# SCH_BME_280_Sensor.net
KiCad netlist of a schematic drawn in EasyEDA
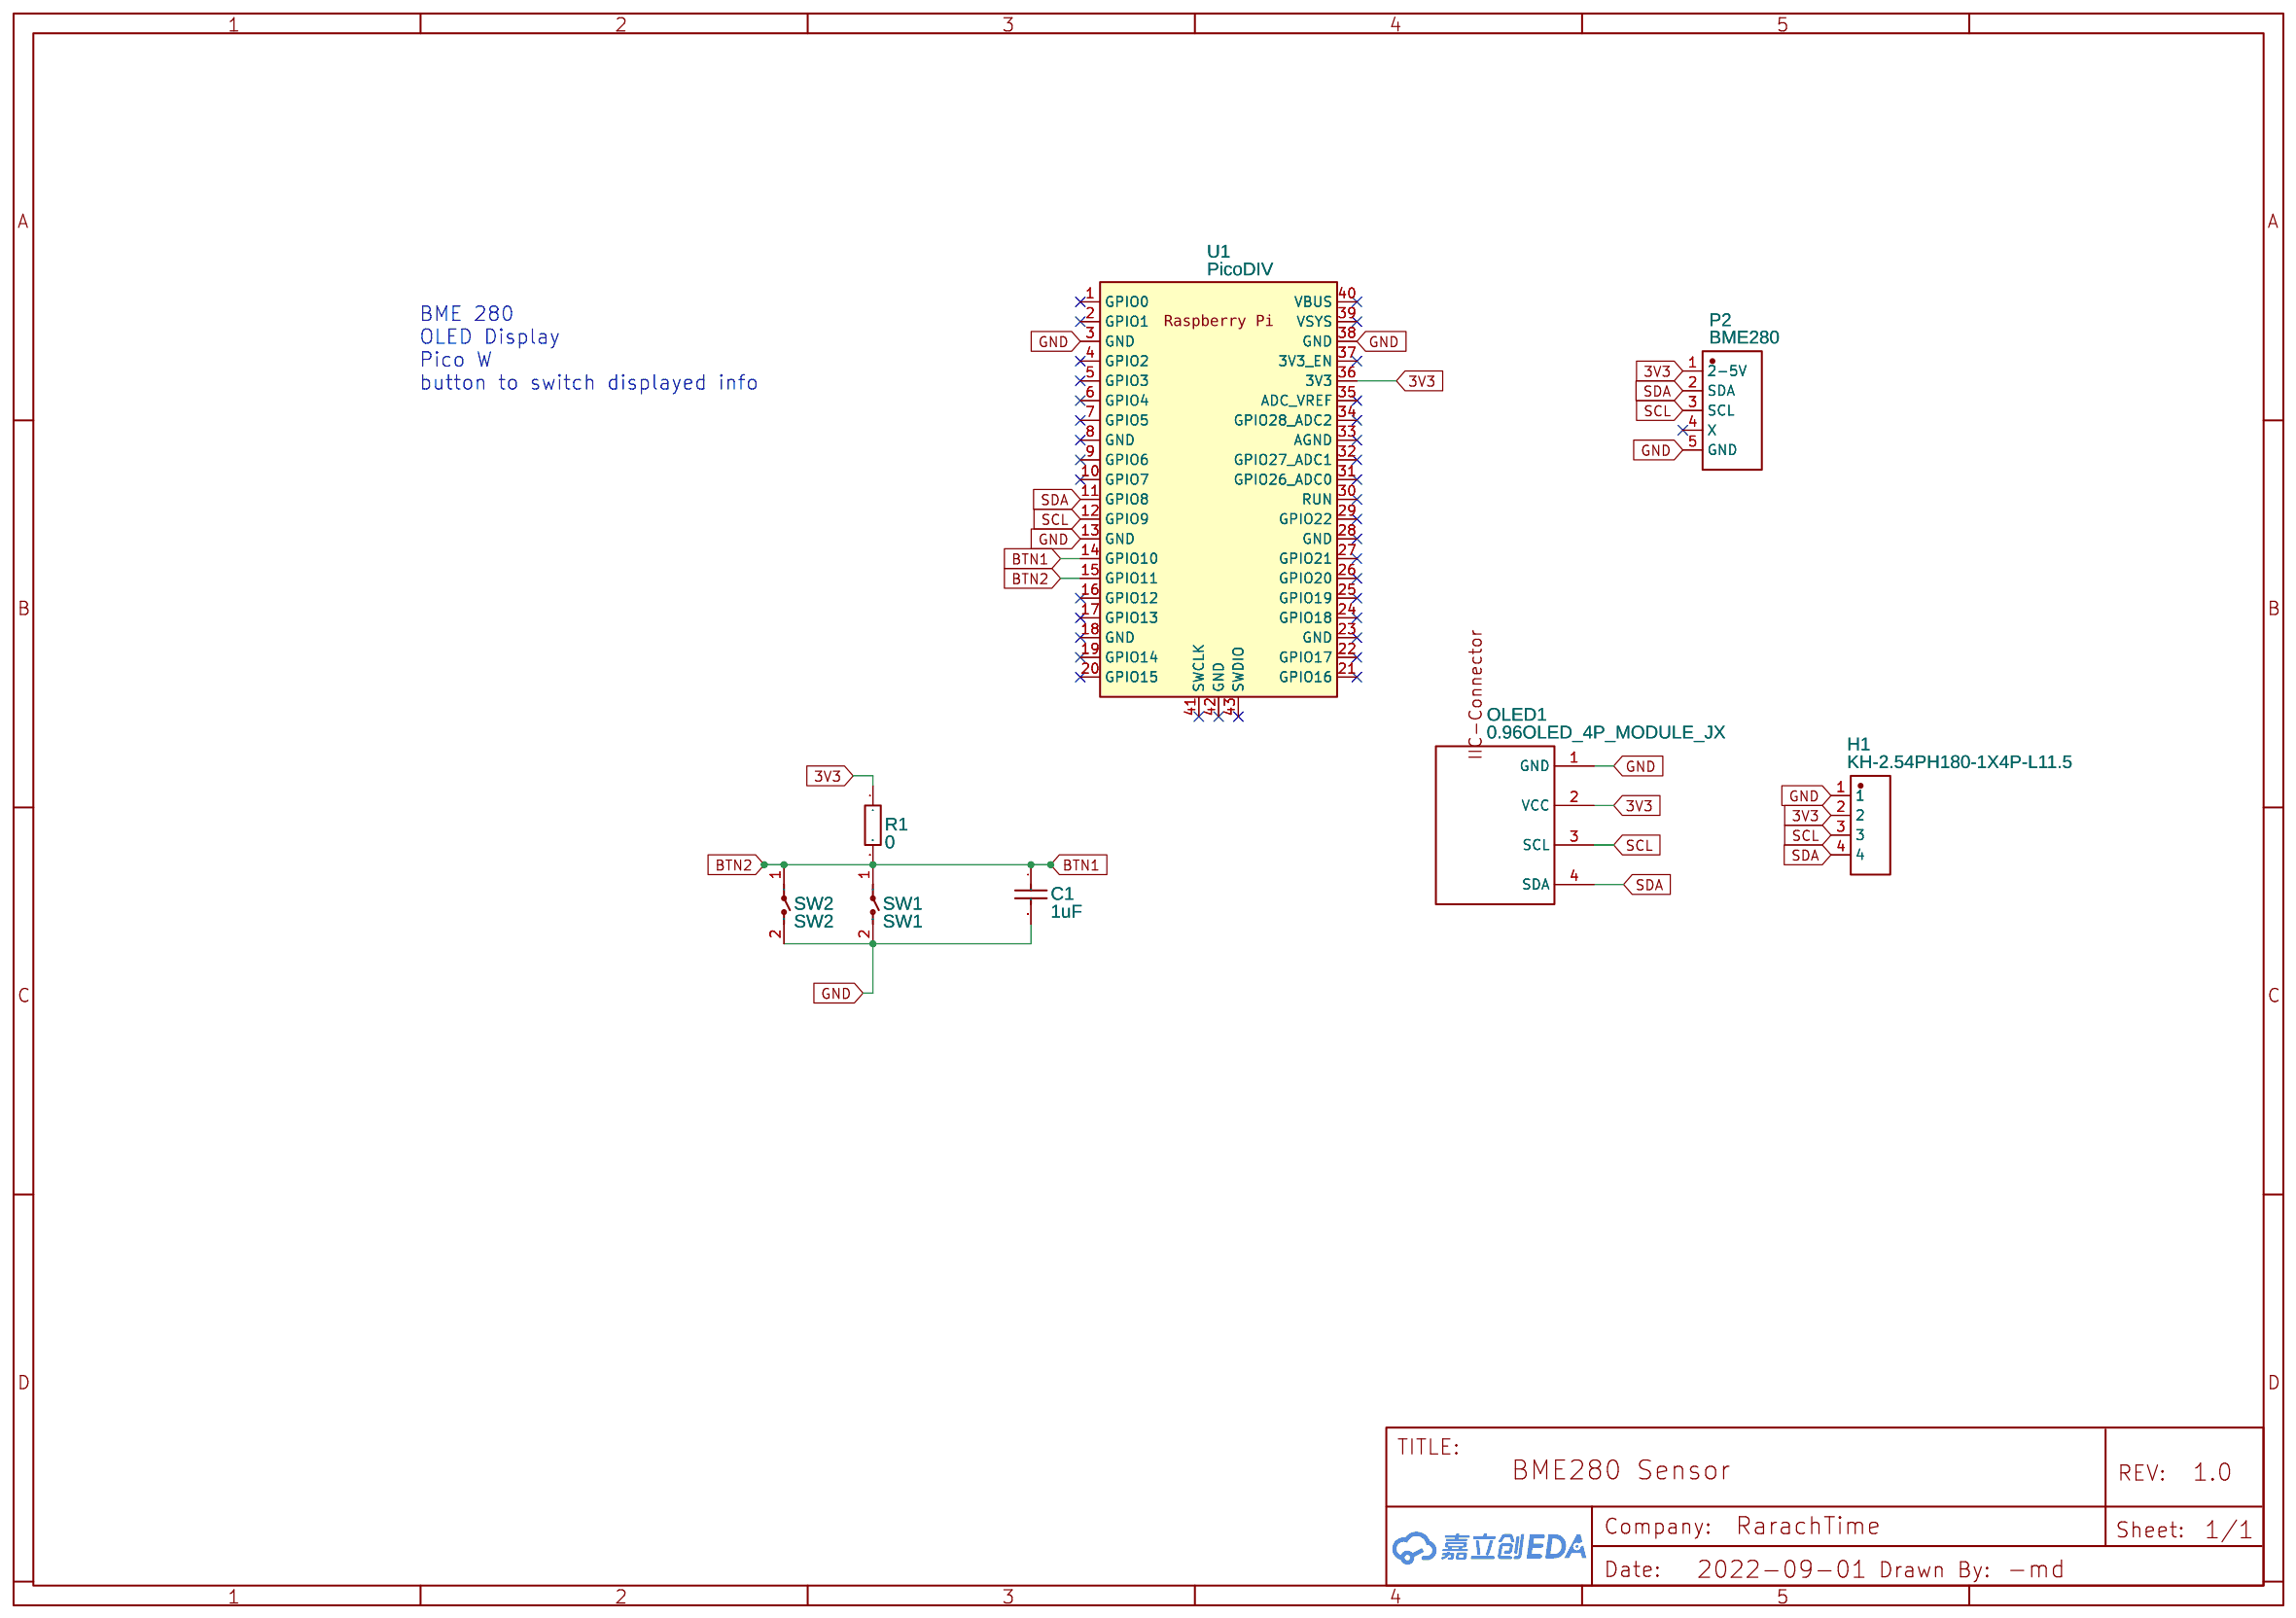
[diagram p0: schematic sheet]

(export (version "E")
  (design (tool "Eeschema 10.0.6"))
  (components
    (comp (ref "C1")
      (value "1uF")
      (fields
        (field (name "BOM_Manufacturer Part") "CL21B105KBFNNNE")
        (field (name "BOM_Supplier Part") "C28323")
      )
      (libsource (lib "") (part "CL21B105KBFNNNE"))
    )
    (comp (ref "H1")
      (value "KH-2.54PH180-1X4P-L11.5")
      (fields (field (name "BOM_Supplier Part") "C2905435"))
      (libsource (lib "") (part "KH-2.54PH180-1X4P-L11.5"))
    )
    (comp (ref "OLED1")
      (value "0.96OLED_4P_MODULE_JX")
      (fields (field (name "BOM_Supplier Part") "C9900004566"))
      (libsource (lib "") (part "0.96OLED_4P_MODULE_JX"))
    )
    (comp (ref "P2")
      (value "BME280")
      (fields
        (field (name "BOM_Manufacturer Part") "2.54mm 1*5P Header")
        (field (name "BOM_Supplier Part") "C50951")
      )
      (libsource (lib "") (part "BME680_PIMORONI"))
    )
    (comp (ref "R1")
      (value "0")
      (fields
        (field (name "BOM_Manufacturer Part") "0805W8F0000T5E")
        (field (name "BOM_Supplier Part") "C17477")
      )
      (libsource (lib "") (part "0805W8F0000T5E"))
    )
    (comp (ref "SW1")
      (value "SW1")
      (fields
        (field (name "BOM_Manufacturer Part") "TS-1001T-AC04316")
        (field (name "BOM_Supplier Part") "C720484")
      )
      (libsource (lib "") (part "TS-1001T-AC04316"))
    )
    (comp (ref "SW2")
      (value "SW2")
      (fields
        (field (name "BOM_Manufacturer Part") "TS-1001T-AC04316")
        (field (name "BOM_Supplier Part") "C720484")
      )
      (libsource (lib "") (part "TS-1001T-AC04316"))
    )
    (comp (ref "U1") (value "PicoDIV") (libsource (lib "") (part "Pico")))
  )
  (nets
    (net (code "1") (name "3V3") (class "Default")
      (node (ref "H1") (pin "2") (pinfunction "2_2") (pintype "unspecified"))
      (node (ref "OLED1") (pin "2") (pinfunction "VCC_2") (pintype "unspecified"))
      (node (ref "P2") (pin "1") (pinfunction "2-5V_1") (pintype "unspecified"))
      (node (ref "R1") (pin "1") (pinfunction "1_1") (pintype "input"))
      (node (ref "U1") (pin "36") (pinfunction "3V3_36") (pintype "unspecified"))
    )
    (net (code "2") (name "BTN1") (class "Default")
      (node (ref "C1") (pin "1") (pinfunction "1_1") (pintype "input"))
      (node (ref "R1") (pin "2") (pinfunction "2_2") (pintype "input"))
      (node (ref "SW1") (pin "1") (pinfunction "1_1") (pintype "unspecified"))
      (node (ref "SW2") (pin "1") (pinfunction "1_1") (pintype "unspecified"))
      (node (ref "U1") (pin "14") (pinfunction "GPIO10_14") (pintype "bidirectional"))
      (node (ref "U1") (pin "15") (pinfunction "GPIO11_15") (pintype "bidirectional"))
    )
    (net (code "3") (name "GND") (class "Default")
      (node (ref "C1") (pin "2") (pinfunction "2_2") (pintype "input"))
      (node (ref "H1") (pin "1") (pinfunction "1_1") (pintype "unspecified"))
      (node (ref "OLED1") (pin "1") (pinfunction "GND_1") (pintype "unspecified"))
      (node (ref "P2") (pin "5") (pinfunction "GND_5") (pintype "unspecified"))
      (node (ref "SW1") (pin "2") (pinfunction "2_2") (pintype "unspecified"))
      (node (ref "SW2") (pin "2") (pinfunction "2_2") (pintype "unspecified"))
      (node (ref "U1") (pin "13") (pinfunction "GND_13") (pintype "bidirectional"))
      (node (ref "U1") (pin "3") (pinfunction "GND_3") (pintype "bidirectional"))
      (node (ref "U1") (pin "38") (pinfunction "GND_38") (pintype "bidirectional"))
    )
    (net (code "4") (name "SCL") (class "Default")
      (node (ref "H1") (pin "3") (pinfunction "3_3") (pintype "unspecified"))
      (node (ref "OLED1") (pin "3") (pinfunction "SCL_3") (pintype "unspecified"))
      (node (ref "P2") (pin "3") (pinfunction "SCL_3") (pintype "unspecified"))
      (node (ref "U1") (pin "12") (pinfunction "GPIO9_12") (pintype "bidirectional"))
    )
    (net (code "5") (name "SDA") (class "Default")
      (node (ref "H1") (pin "4") (pinfunction "4_4") (pintype "unspecified"))
      (node (ref "OLED1") (pin "4") (pinfunction "SDA_4") (pintype "unspecified"))
      (node (ref "P2") (pin "2") (pinfunction "SDA_2") (pintype "unspecified"))
      (node (ref "U1") (pin "11") (pinfunction "GPIO8_11") (pintype "bidirectional"))
    )
    (net (code "6") (name "unconnected-(P2-X-Pad4)") (class "Default")
      (node (ref "P2") (pin "4") (pinfunction "X_4") (pintype "unspecified+no_connect"))
    )
    (net (code "7") (name "unconnected-(U1-3V3_EN-Pad37)") (class "Default")
      (node (ref "U1") (pin "37") (pinfunction "3V3_EN_37") (pintype "input+no_connect"))
    )
    (net (code "8") (name "unconnected-(U1-ADC_VREF-Pad35)") (class "Default")
      (node (ref "U1") (pin "35") (pinfunction "ADC_VREF_35") (pintype "unspecified+no_connect"))
    )
    (net (code "9") (name "unconnected-(U1-AGND-Pad33)") (class "Default")
      (node (ref "U1") (pin "33") (pinfunction "AGND_33") (pintype "bidirectional+no_connect"))
    )
    (net (code "10") (name "unconnected-(U1-GND-Pad8)") (class "Default")
      (node (ref "U1") (pin "8") (pinfunction "GND_8") (pintype "bidirectional+no_connect"))
    )
    (net (code "11") (name "unconnected-(U1-GND-Pad18)") (class "Default")
      (node (ref "U1") (pin "18") (pinfunction "GND_18") (pintype "bidirectional+no_connect"))
    )
    (net (code "12") (name "unconnected-(U1-GND-Pad23)") (class "Default")
      (node (ref "U1") (pin "23") (pinfunction "GND_23") (pintype "bidirectional+no_connect"))
    )
    (net (code "13") (name "unconnected-(U1-GND-Pad28)") (class "Default")
      (node (ref "U1") (pin "28") (pinfunction "GND_28") (pintype "bidirectional+no_connect"))
    )
    (net (code "14") (name "unconnected-(U1-GND-Pad42)") (class "Default")
      (node (ref "U1") (pin "42") (pinfunction "GND_42") (pintype "bidirectional+no_connect"))
    )
    (net (code "15") (name "unconnected-(U1-GPIO0-Pad1)") (class "Default")
      (node (ref "U1") (pin "1") (pinfunction "GPIO0_1") (pintype "bidirectional+no_connect"))
    )
    (net (code "16") (name "unconnected-(U1-GPIO1-Pad2)") (class "Default")
      (node (ref "U1") (pin "2") (pinfunction "GPIO1_2") (pintype "bidirectional+no_connect"))
    )
    (net (code "17") (name "unconnected-(U1-GPIO2-Pad4)") (class "Default")
      (node (ref "U1") (pin "4") (pinfunction "GPIO2_4") (pintype "bidirectional+no_connect"))
    )
    (net (code "18") (name "unconnected-(U1-GPIO3-Pad5)") (class "Default")
      (node (ref "U1") (pin "5") (pinfunction "GPIO3_5") (pintype "bidirectional+no_connect"))
    )
    (net (code "19") (name "unconnected-(U1-GPIO4-Pad6)") (class "Default")
      (node (ref "U1") (pin "6") (pinfunction "GPIO4_6") (pintype "bidirectional+no_connect"))
    )
    (net (code "20") (name "unconnected-(U1-GPIO5-Pad7)") (class "Default")
      (node (ref "U1") (pin "7") (pinfunction "GPIO5_7") (pintype "bidirectional+no_connect"))
    )
    (net (code "21") (name "unconnected-(U1-GPIO6-Pad9)") (class "Default")
      (node (ref "U1") (pin "9") (pinfunction "GPIO6_9") (pintype "bidirectional+no_connect"))
    )
    (net (code "22") (name "unconnected-(U1-GPIO7-Pad10)") (class "Default")
      (node (ref "U1") (pin "10") (pinfunction "GPIO7_10") (pintype "bidirectional+no_connect"))
    )
    (net (code "23") (name "unconnected-(U1-GPIO12-Pad16)") (class "Default")
      (node (ref "U1") (pin "16") (pinfunction "GPIO12_16") (pintype "bidirectional+no_connect"))
    )
    (net (code "24") (name "unconnected-(U1-GPIO13-Pad17)") (class "Default")
      (node (ref "U1") (pin "17") (pinfunction "GPIO13_17") (pintype "bidirectional+no_connect"))
    )
    (net (code "25") (name "unconnected-(U1-GPIO14-Pad19)") (class "Default")
      (node (ref "U1") (pin "19") (pinfunction "GPIO14_19") (pintype "bidirectional+no_connect"))
    )
    (net (code "26") (name "unconnected-(U1-GPIO15-Pad20)") (class "Default")
      (node (ref "U1") (pin "20") (pinfunction "GPIO15_20") (pintype "bidirectional+no_connect"))
    )
    (net (code "27") (name "unconnected-(U1-GPIO16-Pad21)") (class "Default")
      (node (ref "U1") (pin "21") (pinfunction "GPIO16_21") (pintype "bidirectional+no_connect"))
    )
    (net (code "28") (name "unconnected-(U1-GPIO17-Pad22)") (class "Default")
      (node (ref "U1") (pin "22") (pinfunction "GPIO17_22") (pintype "bidirectional+no_connect"))
    )
    (net (code "29") (name "unconnected-(U1-GPIO18-Pad24)") (class "Default")
      (node (ref "U1") (pin "24") (pinfunction "GPIO18_24") (pintype "bidirectional+no_connect"))
    )
    (net (code "30") (name "unconnected-(U1-GPIO19-Pad25)") (class "Default")
      (node (ref "U1") (pin "25") (pinfunction "GPIO19_25") (pintype "bidirectional+no_connect"))
    )
    (net (code "31") (name "unconnected-(U1-GPIO20-Pad26)") (class "Default")
      (node (ref "U1") (pin "26") (pinfunction "GPIO20_26") (pintype "bidirectional+no_connect"))
    )
    (net (code "32") (name "unconnected-(U1-GPIO21-Pad27)") (class "Default")
      (node (ref "U1") (pin "27") (pinfunction "GPIO21_27") (pintype "bidirectional+no_connect"))
    )
    (net (code "33") (name "unconnected-(U1-GPIO22-Pad29)") (class "Default")
      (node (ref "U1") (pin "29") (pinfunction "GPIO22_29") (pintype "bidirectional+no_connect"))
    )
    (net (code "34") (name "unconnected-(U1-GPIO26_ADC0-Pad31)") (class "Default")
      (node (ref "U1") (pin "31") (pinfunction "GPIO26_ADC0_31") (pintype "bidirectional+no_connect"))
    )
    (net (code "35") (name "unconnected-(U1-GPIO27_ADC1-Pad32)") (class "Default")
      (node (ref "U1") (pin "32") (pinfunction "GPIO27_ADC1_32") (pintype "bidirectional+no_connect"))
    )
    (net (code "36") (name "unconnected-(U1-GPIO28_ADC2-Pad34)") (class "Default")
      (node (ref "U1") (pin "34") (pinfunction "GPIO28_ADC2_34") (pintype "bidirectional+no_connect"))
    )
    (net (code "37") (name "unconnected-(U1-RUN-Pad30)") (class "Default")
      (node (ref "U1") (pin "30") (pinfunction "RUN_30") (pintype "input+no_connect"))
    )
    (net (code "38") (name "unconnected-(U1-SWCLK-Pad41)") (class "Default")
      (node (ref "U1") (pin "41") (pinfunction "SWCLK_41") (pintype "input+no_connect"))
    )
    (net (code "39") (name "unconnected-(U1-SWDIO-Pad43)") (class "Default")
      (node (ref "U1") (pin "43") (pinfunction "SWDIO_43") (pintype "bidirectional+no_connect"))
    )
    (net (code "40") (name "unconnected-(U1-VBUS-Pad40)") (class "Default")
      (node (ref "U1") (pin "40") (pinfunction "VBUS_40") (pintype "unspecified+no_connect"))
    )
    (net (code "41") (name "unconnected-(U1-VSYS-Pad39)") (class "Default")
      (node (ref "U1") (pin "39") (pinfunction "VSYS_39") (pintype "unspecified+no_connect"))
    )
  )
)
